# schematic.net
KiCad netlist of a schematic drawn in Altium Designer
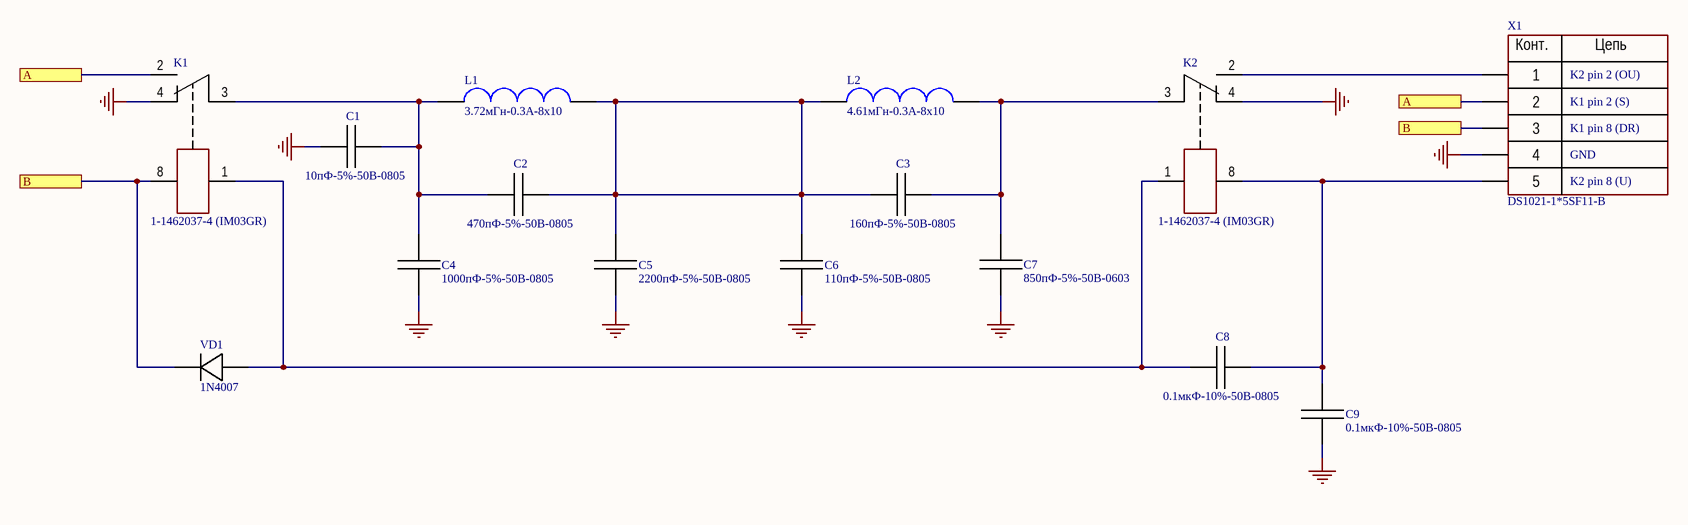
[diagram p0: schematic.SchDoc]

(export (version "E")
  (design (tool "Eeschema 10.0.6"))
  (components
    (comp (ref "C1")
      (value "10пФ-5%-50В-0805")
      (footprint "capacitor_0805")
      (fields
        (field (name "MANUFACTURER") "Murata Electronics")
        (field (name "PARTNUMBER") "GRM2165C1H100JZ01D")
      )
      (libsource (lib "schematic_library") (part "Capacitor"))
    )
    (comp (ref "C2")
      (value "470пФ-5%-50В-0805")
      (footprint "capacitor_0805")
      (fields
        (field (name "MANUFACTURER") "Murata Electronics")
        (field (name "PARTNUMBER") "GRM2165C1H471JA01D")
      )
      (libsource (lib "schematic_library") (part "Capacitor"))
    )
    (comp (ref "C3")
      (value "160пФ-5%-50В-0805")
      (footprint "capacitor_0805")
      (fields (field (name "MANUFACTURER") "Тайвань") (field (name "PARTNUMBER") "MLCC160pFNPO50V5%0805"))
      (libsource (lib "schematic_library") (part "Capacitor"))
    )
    (comp (ref "C4")
      (value "1000пФ-5%-50В-0805")
      (footprint "capacitor_0805")
      (fields
        (field (name "MANUFACTURER") "Murata Electronics")
        (field (name "PARTNUMBER") "GRM2165C1H102JA01D")
      )
      (libsource (lib "schematic_library") (part "Capacitor"))
    )
    (comp (ref "C5")
      (value "2200пФ-5%-50В-0805")
      (footprint "capacitor_0805")
      (fields
        (field (name "MANUFACTURER") "Murata Electronics")
        (field (name "PARTNUMBER") "GRM2165C1H222JA01D")
      )
      (libsource (lib "schematic_library") (part "Capacitor"))
    )
    (comp (ref "C6")
      (value "110пФ-5%-50В-0805")
      (footprint "capacitor_0805")
      (fields (field (name "MANUFACTURER") "Тайвань") (field (name "PARTNUMBER") "MLCC110pFNPO50V5%0805"))
      (libsource (lib "schematic_library") (part "Capacitor"))
    )
    (comp (ref "C7")
      (value "850пФ-5%-50В-0603")
      (footprint "capacitor_0603")
      (fields (field (name "MANUFACTURER") "Knowles Novacap") (field (name "PARTNUMBER") "C06BL851X-1SN-X0T"))
      (libsource (lib "schematic_library") (part "Capacitor"))
    )
    (comp (ref "C8")
      (value "0.1мкФ-10%-50В-0805")
      (footprint "capacitor_0805")
      (fields
        (field (name "MANUFACTURER") "Murata Electronics")
        (field (name "PARTNUMBER") "GRM21BR71H104KA01L")
      )
      (libsource (lib "schematic_library") (part "Capacitor"))
    )
    (comp (ref "C9")
      (value "0.1мкФ-10%-50В-0805")
      (footprint "capacitor_0805")
      (fields
        (field (name "MANUFACTURER") "Murata Electronics")
        (field (name "PARTNUMBER") "GRM21BR71H104KA01L")
      )
      (libsource (lib "schematic_library") (part "Capacitor"))
    )
    (comp (ref "K1")
      (value "1-1462037-4 (IM03GR)")
      (footprint "RELAY_IM03GR")
      (libsource (lib "schematic_library") (part "Realy_IM03GR"))
    )
    (comp (ref "K2")
      (value "1-1462037-4 (IM03GR)")
      (footprint "RELAY_IM03GR")
      (libsource (lib "") (part "Realy_IM03GR_1"))
    )
    (comp (ref "L1")
      (value "3.72мГн-0.3А-8x10")
      (footprint "inductor_0810")
      (fields (field (name "PARTNUMBER") "0810") (field (name "MANUFACTURER") "FGHGF"))
      (libsource (lib "schematic_library") (part "Inductor"))
    )
    (comp (ref "L2")
      (value "4.61мГн-0.3А-8x10")
      (footprint "inductor_0810")
      (fields (field (name "PARTNUMBER") "0810") (field (name "MANUFACTURER") "FGHGF"))
      (libsource (lib "schematic_library") (part "Inductor"))
    )
    (comp (ref "VD1")
      (value "1N4007")
      (footprint "DIODE_DO41")
      (fields (field (name "MANUFACTURER") "Diotec Semiconductor"))
      (libsource (lib "schematic_library") (part "Diode"))
    )
    (comp (ref "X1")
      (value "DS1021-1*5SF11-B")
      (footprint "connector_5_pls")
      (fields (field (name "MANUFACTURER") "Connfly electronic (Zhenqin)"))
      (libsource (lib "schematic_library") (part "Connector_5"))
    )
  )
  (nets
    (net (code "1") (name "/A") (class "Default")
      (node (ref "K1") (pin "2") (pinfunction "2_2") (pintype "passive"))
      (node (ref "X1") (pin "2") (pinfunction "2_2") (pintype "passive"))
    )
    (net (code "2") (name "/B") (class "Default")
      (node (ref "K1") (pin "8") (pinfunction "8_8") (pintype "passive"))
      (node (ref "VD1") (pin "1") (pinfunction "1_1") (pintype "passive"))
      (node (ref "X1") (pin "3") (pinfunction "3_3") (pintype "power_in"))
    )
    (net (code "3") (name "GND") (class "Default")
      (node (ref "C1") (pin "0") (pinfunction "0_0") (pintype "passive"))
      (node (ref "C4") (pin "1") (pinfunction "1_1") (pintype "passive"))
      (node (ref "C5") (pin "1") (pinfunction "1_1") (pintype "passive"))
      (node (ref "C6") (pin "1") (pinfunction "1_1") (pintype "passive"))
      (node (ref "C7") (pin "0") (pinfunction "0_0") (pintype "passive"))
      (node (ref "C9") (pin "1") (pinfunction "1_1") (pintype "passive"))
      (node (ref "K1") (pin "4") (pinfunction "4_4") (pintype "passive"))
      (node (ref "K2") (pin "4") (pinfunction "4_4") (pintype "passive"))
      (node (ref "X1") (pin "4") (pinfunction "4_4") (pintype "power_in"))
    )
    (net (code "4") (name "Net-(C2-Pad1)") (class "Default")
      (node (ref "C2") (pin "1") (pinfunction "1_1") (pintype "passive"))
      (node (ref "C3") (pin "0") (pinfunction "0_0") (pintype "passive"))
      (node (ref "C5") (pin "0") (pinfunction "0_0") (pintype "passive"))
      (node (ref "C6") (pin "0") (pinfunction "0_0") (pintype "passive"))
      (node (ref "L1") (pin "1") (pinfunction "1_1") (pintype "passive"))
      (node (ref "L2") (pin "0") (pinfunction "0_0") (pintype "passive"))
    )
    (net (code "5") (name "Net-(C8-Pad0)") (class "Default")
      (node (ref "C8") (pin "0") (pinfunction "0_0") (pintype "passive"))
      (node (ref "K1") (pin "1") (pinfunction "1_1") (pintype "passive"))
      (node (ref "K2") (pin "1") (pinfunction "1_1") (pintype "passive"))
      (node (ref "VD1") (pin "0") (pinfunction "0_0") (pintype "passive"))
    )
    (net (code "6") (name "Net-(C8-Pad1)") (class "Default")
      (node (ref "C8") (pin "1") (pinfunction "1_1") (pintype "passive"))
      (node (ref "C9") (pin "0") (pinfunction "0_0") (pintype "passive"))
      (node (ref "K2") (pin "8") (pinfunction "8_8") (pintype "passive"))
      (node (ref "X1") (pin "5") (pinfunction "5_5") (pintype "power_in"))
    )
    (net (code "7") (name "Net-(K1-3(6))") (class "Default")
      (node (ref "C1") (pin "1") (pinfunction "1_1") (pintype "passive"))
      (node (ref "C2") (pin "0") (pinfunction "0_0") (pintype "passive"))
      (node (ref "C4") (pin "0") (pinfunction "0_0") (pintype "passive"))
      (node (ref "K1") (pin "3") (pinfunction "3(6)_3") (pintype "passive"))
      (node (ref "L1") (pin "0") (pinfunction "0_0") (pintype "passive"))
    )
    (net (code "8") (name "Net-(K2-3(6))") (class "Default")
      (node (ref "C3") (pin "1") (pinfunction "1_1") (pintype "passive"))
      (node (ref "C7") (pin "1") (pinfunction "1_1") (pintype "passive"))
      (node (ref "K2") (pin "3") (pinfunction "3(6)_3") (pintype "passive"))
      (node (ref "L2") (pin "1") (pinfunction "1_1") (pintype "passive"))
    )
    (net (code "9") (name "Net-(K2-Pad2)") (class "Default")
      (node (ref "K2") (pin "2") (pinfunction "2_2") (pintype "passive"))
      (node (ref "X1") (pin "1") (pinfunction "1_1") (pintype "passive"))
    )
  )
)
